# poor_man_DWM1001.net
KiCad netlist of a schematic drawn in EAGLE
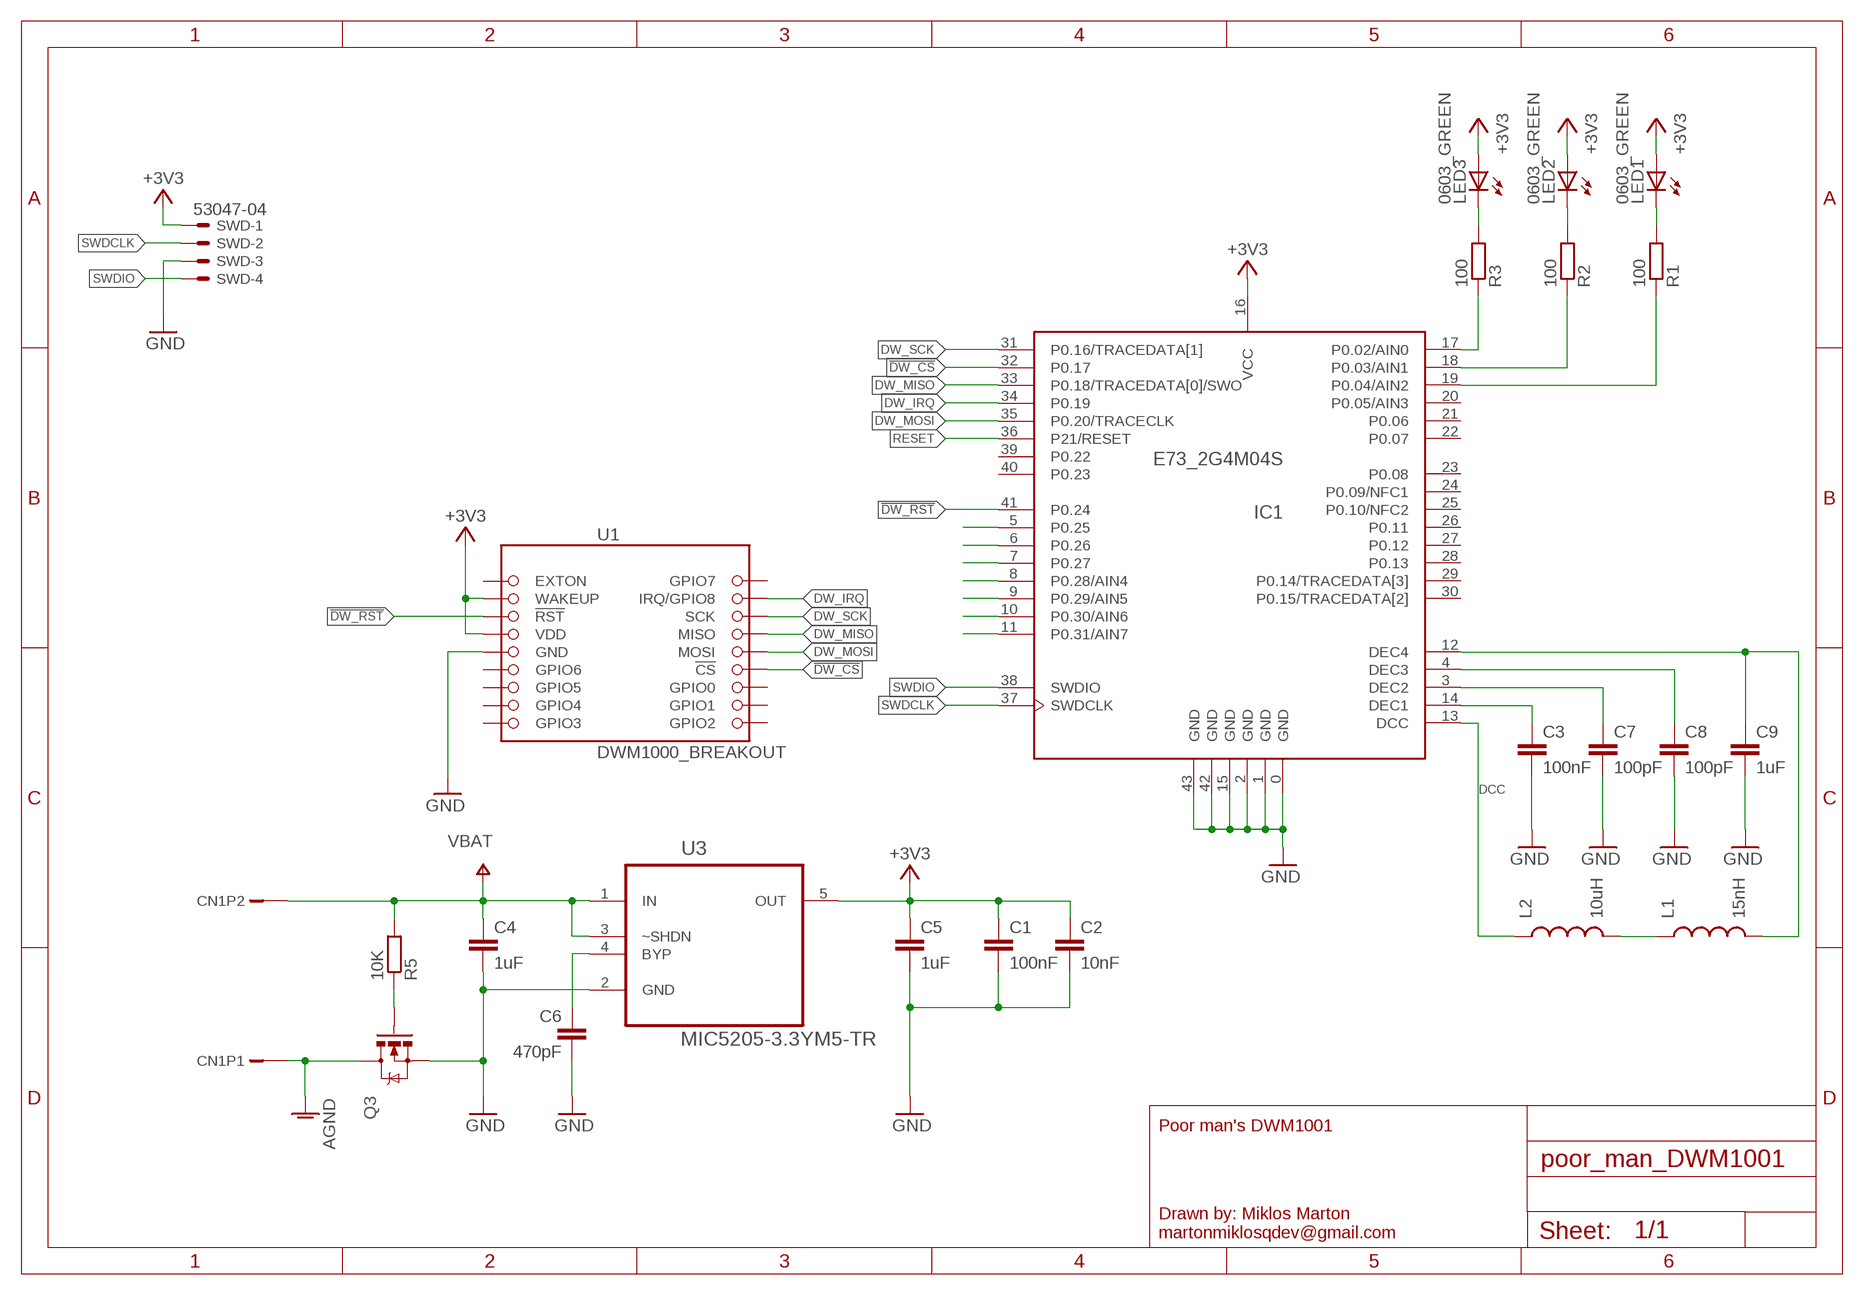
[diagram p0: schematic, sheet 1]

(export (version "E")
  (design (tool "Eeschema 10.0.6"))
  (components
    (comp (ref "C1")
      (value "100nF")
      (footprint "eagle-import:C0603")
      (libsource (lib "eagle-import") (part "C-EUC0603"))
    )
    (comp (ref "C2")
      (value "10nF")
      (footprint "eagle-import:C0603")
      (libsource (lib "eagle-import") (part "C-EUC0603"))
    )
    (comp (ref "C3")
      (value "100nF")
      (footprint "eagle-import:C0603")
      (libsource (lib "eagle-import") (part "C-EUC0603"))
    )
    (comp (ref "C4")
      (value "1uF")
      (footprint "eagle-import:C0603")
      (libsource (lib "eagle-import") (part "C-EUC0603"))
    )
    (comp (ref "C5")
      (value "1uF")
      (footprint "eagle-import:C0603")
      (libsource (lib "eagle-import") (part "C-EUC0603"))
    )
    (comp (ref "C6")
      (value "470pF")
      (footprint "eagle-import:C0603")
      (libsource (lib "eagle-import") (part "C-EUC0603"))
    )
    (comp (ref "C7")
      (value "100pF")
      (footprint "eagle-import:C0603")
      (libsource (lib "eagle-import") (part "C-EUC0603"))
    )
    (comp (ref "C8")
      (value "100pF")
      (footprint "eagle-import:C0603")
      (libsource (lib "eagle-import") (part "C-EUC0603"))
    )
    (comp (ref "C9")
      (value "1uF")
      (footprint "eagle-import:C0603")
      (libsource (lib "eagle-import") (part "C-EUC0603"))
    )
    (comp (ref "CN1")
      (value "B2B-PH-K-S")
      (footprint "eagle-import:B2B-PH-K-S")
      (libsource (lib "eagle-import") (part "B2B-PH-K-S"))
    )
    (comp (ref "IC1")
      (value "E73_2G4M04S")
      (footprint "eagle-import:E73_2G4M04S")
      (libsource (lib "eagle-import") (part "E73_2G4M04S"))
    )
    (comp (ref "L1")
      (value "15nH")
      (footprint "eagle-import:SPARKFUN_C0402")
      (libsource (lib "eagle-import") (part "SPARKFUN_INDUCTOR0402"))
    )
    (comp (ref "L2")
      (value "10uH")
      (footprint "eagle-import:SPARKFUN_0603")
      (libsource (lib "eagle-import") (part "SPARKFUN_INDUCTOR0603"))
    )
    (comp (ref "LED1")
      (value "0603_GREEN")
      (footprint "eagle-import:CHIP-LED0603")
      (libsource (lib "eagle-import") (part "LEDCHIP-LED0603"))
    )
    (comp (ref "LED2")
      (value "0603_GREEN")
      (footprint "eagle-import:CHIP-LED0603")
      (libsource (lib "eagle-import") (part "LEDCHIP-LED0603"))
    )
    (comp (ref "LED3")
      (value "0603_GREEN")
      (footprint "eagle-import:CHIP-LED0603")
      (libsource (lib "eagle-import") (part "LEDCHIP-LED0603"))
    )
    (comp (ref "Q3")
      (value "MOSFET-NCHANNELSMD")
      (footprint "eagle-import:SOT23-3")
      (libsource (lib "eagle-import") (part "MOSFET-NCHANNELSMD"))
    )
    (comp (ref "R1")
      (value "100")
      (footprint "eagle-import:R0603")
      (libsource (lib "eagle-import") (part "R-EU_R0603"))
    )
    (comp (ref "R2")
      (value "100")
      (footprint "eagle-import:R0603")
      (libsource (lib "eagle-import") (part "R-EU_R0603"))
    )
    (comp (ref "R3")
      (value "100")
      (footprint "eagle-import:R0603")
      (libsource (lib "eagle-import") (part "R-EU_R0603"))
    )
    (comp (ref "R5")
      (value "10K")
      (footprint "eagle-import:R0603")
      (libsource (lib "eagle-import") (part "R-EU_R0603"))
    )
    (comp (ref "SWD")
      (value "53047-04")
      (footprint "eagle-import:53047-04")
      (fields (field (name "MF") "WALDOM/MOLEX") (field (name "MPN") "53047-0410"))
      (libsource (lib "eagle-import") (part "53?-04047"))
    )
    (comp (ref "U1")
      (value "DWM1000_BREAKOUT")
      (footprint "eagle-import:DWM1000_BREAKOUT")
      (libsource (lib "eagle-import") (part "DWM1000_BREAKOUT"))
    )
    (comp (ref "U3")
      (value "MIC5205-3.3YM5-TR")
      (footprint "eagle-import:SOT95P280X145-5N")
      (fields (field (name "MPN") "LT1761ES5-3.3#TRMPBF"))
      (libsource (lib "eagle-import") (part "LT1761ES5-3.3TRMPBF"))
    )
  )
  (nets
    (net (code "1") (name "+3V3") (class "Default")
      (node (ref "C1") (pin "1") (pinfunction "1_1") (pintype "passive"))
      (node (ref "C2") (pin "1") (pinfunction "1_1") (pintype "passive"))
      (node (ref "C5") (pin "1") (pinfunction "1_1") (pintype "passive"))
      (node (ref "IC1") (pin "16") (pinfunction "VCC_16") (pintype "passive"))
      (node (ref "LED1") (pin "A") (pinfunction "A_A") (pintype "passive"))
      (node (ref "LED2") (pin "A") (pinfunction "A_A") (pintype "passive"))
      (node (ref "LED3") (pin "A") (pinfunction "A_A") (pintype "passive"))
      (node (ref "SWD") (pin "1") (pinfunction "S_1") (pintype "passive"))
      (node (ref "U1") (pin "15") (pinfunction "VDD_15") (pintype "passive"))
      (node (ref "U1") (pin "17") (pinfunction "WAKEUP_17") (pintype "passive"))
      (node (ref "U3") (pin "5") (pinfunction "OUT_5") (pintype "passive"))
    )
    (net (code "2") (name "/DCC") (class "Default")
      (node (ref "IC1") (pin "13") (pinfunction "DCC_13") (pintype "power_in"))
      (node (ref "L2") (pin "1") (pinfunction "1_1") (pintype "passive"))
    )
    (net (code "3") (name "/~{DW_CS}") (class "Default")
      (node (ref "IC1") (pin "32") (pinfunction "P0.17_32") (pintype "bidirectional"))
      (node (ref "U1") (pin "6") (pinfunction "~{CS}_6") (pintype "input"))
    )
    (net (code "4") (name "/~{DW_RST}") (class "Default")
      (node (ref "IC1") (pin "41") (pinfunction "P0.24_41") (pintype "bidirectional"))
      (node (ref "U1") (pin "16") (pinfunction "~{RST}_16") (pintype "input"))
    )
    (net (code "5") (name "AGND") (class "Default")
      (node (ref "CN1") (pin "1") (pinfunction "1_1") (pintype "passive"))
      (node (ref "Q3") (pin "3") (pinfunction "D_3") (pintype "passive"))
    )
    (net (code "6") (name "DW_IRQ") (class "Default")
      (node (ref "IC1") (pin "34") (pinfunction "P0.19_34") (pintype "bidirectional"))
      (node (ref "U1") (pin "2") (pinfunction "IRQ/GPIO8_2") (pintype "passive"))
    )
    (net (code "7") (name "DW_MISO") (class "Default")
      (node (ref "IC1") (pin "33") (pinfunction "P0.18/TRACEDATA[0]/SWO_33") (pintype "bidirectional"))
      (node (ref "U1") (pin "4") (pinfunction "MISO_4") (pintype "passive"))
    )
    (net (code "8") (name "DW_MOSI") (class "Default")
      (node (ref "IC1") (pin "35") (pinfunction "P0.20/TRACECLK_35") (pintype "bidirectional"))
      (node (ref "U1") (pin "5") (pinfunction "MOSI_5") (pintype "passive"))
    )
    (net (code "9") (name "DW_SCK") (class "Default")
      (node (ref "IC1") (pin "31") (pinfunction "P0.16/TRACEDATA[1]_31") (pintype "bidirectional"))
      (node (ref "U1") (pin "3") (pinfunction "SCK_3") (pintype "passive"))
    )
    (net (code "10") (name "GND") (class "Default")
      (node (ref "C1") (pin "2") (pinfunction "2_2") (pintype "passive"))
      (node (ref "C2") (pin "2") (pinfunction "2_2") (pintype "passive"))
      (node (ref "C3") (pin "2") (pinfunction "2_2") (pintype "passive"))
      (node (ref "C4") (pin "2") (pinfunction "2_2") (pintype "passive"))
      (node (ref "C5") (pin "2") (pinfunction "2_2") (pintype "passive"))
      (node (ref "C6") (pin "2") (pinfunction "2_2") (pintype "passive"))
      (node (ref "C7") (pin "2") (pinfunction "2_2") (pintype "passive"))
      (node (ref "C8") (pin "2") (pinfunction "2_2") (pintype "passive"))
      (node (ref "C9") (pin "2") (pinfunction "2_2") (pintype "passive"))
      (node (ref "IC1") (pin "0") (pinfunction "GND_0") (pintype "bidirectional"))
      (node (ref "IC1") (pin "1") (pinfunction "GND_1") (pintype "bidirectional"))
      (node (ref "IC1") (pin "15") (pinfunction "GND_15") (pintype "bidirectional"))
      (node (ref "IC1") (pin "2") (pinfunction "GND_2") (pintype "bidirectional"))
      (node (ref "IC1") (pin "42") (pinfunction "GND_42") (pintype "bidirectional"))
      (node (ref "IC1") (pin "43") (pinfunction "GND_43") (pintype "bidirectional"))
      (node (ref "Q3") (pin "2") (pinfunction "S_2") (pintype "passive"))
      (node (ref "SWD") (pin "3") (pinfunction "S_3") (pintype "passive"))
      (node (ref "U1") (pin "14") (pinfunction "GND_14") (pintype "passive"))
      (node (ref "U3") (pin "2") (pinfunction "GND_2") (pintype "passive"))
    )
    (net (code "11") (name "Net-(IC1-DEC1)") (class "Default")
      (node (ref "C3") (pin "1") (pinfunction "1_1") (pintype "passive"))
      (node (ref "IC1") (pin "14") (pinfunction "DEC1_14") (pintype "power_in"))
    )
    (net (code "12") (name "Net-(IC1-DEC2)") (class "Default")
      (node (ref "C7") (pin "1") (pinfunction "1_1") (pintype "passive"))
      (node (ref "IC1") (pin "3") (pinfunction "DEC2_3") (pintype "power_in"))
    )
    (net (code "13") (name "Net-(IC1-DEC3)") (class "Default")
      (node (ref "C8") (pin "1") (pinfunction "1_1") (pintype "passive"))
      (node (ref "IC1") (pin "4") (pinfunction "DEC3_4") (pintype "power_in"))
    )
    (net (code "14") (name "Net-(IC1-DEC4)") (class "Default")
      (node (ref "C9") (pin "1") (pinfunction "1_1") (pintype "passive"))
      (node (ref "IC1") (pin "12") (pinfunction "DEC4_12") (pintype "power_in"))
      (node (ref "L1") (pin "2") (pinfunction "2_2") (pintype "passive"))
    )
    (net (code "15") (name "Net-(IC1-P0.02{slash}AIN0)") (class "Default")
      (node (ref "IC1") (pin "17") (pinfunction "P0.02/AIN0_17") (pintype "bidirectional"))
      (node (ref "R3") (pin "1") (pinfunction "1_1") (pintype "passive"))
    )
    (net (code "16") (name "Net-(IC1-P0.03{slash}AIN1)") (class "Default")
      (node (ref "IC1") (pin "18") (pinfunction "P0.03/AIN1_18") (pintype "bidirectional"))
      (node (ref "R2") (pin "1") (pinfunction "1_1") (pintype "passive"))
    )
    (net (code "17") (name "Net-(IC1-P0.04{slash}AIN2)") (class "Default")
      (node (ref "IC1") (pin "19") (pinfunction "P0.04/AIN2_19") (pintype "bidirectional"))
      (node (ref "R1") (pin "1") (pinfunction "1_1") (pintype "passive"))
    )
    (net (code "18") (name "Net-(L1-Pad1)") (class "Default")
      (node (ref "L1") (pin "1") (pinfunction "1_1") (pintype "passive"))
      (node (ref "L2") (pin "2") (pinfunction "2_2") (pintype "passive"))
    )
    (net (code "19") (name "Net-(LED1-PadC)") (class "Default")
      (node (ref "LED1") (pin "C") (pinfunction "C_C") (pintype "passive"))
      (node (ref "R1") (pin "2") (pinfunction "2_2") (pintype "passive"))
    )
    (net (code "20") (name "Net-(LED2-PadC)") (class "Default")
      (node (ref "LED2") (pin "C") (pinfunction "C_C") (pintype "passive"))
      (node (ref "R2") (pin "2") (pinfunction "2_2") (pintype "passive"))
    )
    (net (code "21") (name "Net-(LED3-PadC)") (class "Default")
      (node (ref "LED3") (pin "C") (pinfunction "C_C") (pintype "passive"))
      (node (ref "R3") (pin "2") (pinfunction "2_2") (pintype "passive"))
    )
    (net (code "22") (name "Net-(Q3-G)") (class "Default")
      (node (ref "Q3") (pin "1") (pinfunction "G_1") (pintype "passive"))
      (node (ref "R5") (pin "1") (pinfunction "1_1") (pintype "passive"))
    )
    (net (code "23") (name "Net-(U3-BYP)") (class "Default")
      (node (ref "C6") (pin "1") (pinfunction "1_1") (pintype "passive"))
      (node (ref "U3") (pin "4") (pinfunction "BYP_4") (pintype "passive"))
    )
    (net (code "24") (name "RESET") (class "Default")
      (node (ref "IC1") (pin "36") (pinfunction "P21/RESET_36") (pintype "bidirectional"))
    )
    (net (code "25") (name "SWDCLK") (class "Default")
      (node (ref "IC1") (pin "37") (pinfunction "SWDCLK_37") (pintype "input"))
      (node (ref "SWD") (pin "2") (pinfunction "S_2") (pintype "passive"))
    )
    (net (code "26") (name "SWDIO") (class "Default")
      (node (ref "IC1") (pin "38") (pinfunction "SWDIO_38") (pintype "bidirectional"))
      (node (ref "SWD") (pin "4") (pinfunction "S_4") (pintype "passive"))
    )
    (net (code "27") (name "VBAT") (class "Default")
      (node (ref "C4") (pin "1") (pinfunction "1_1") (pintype "passive"))
      (node (ref "CN1") (pin "2") (pinfunction "1_2") (pintype "passive"))
      (node (ref "R5") (pin "2") (pinfunction "2_2") (pintype "passive"))
      (node (ref "U3") (pin "1") (pinfunction "IN_1") (pintype "power_in"))
      (node (ref "U3") (pin "3") (pinfunction "~{SHDN}_3") (pintype "input"))
    )
    (net (code "28") (name "unconnected-(IC1-P0.05{slash}AIN3-Pad20)") (class "Default")
      (node (ref "IC1") (pin "20") (pinfunction "P0.05/AIN3_20") (pintype "bidirectional"))
    )
    (net (code "29") (name "unconnected-(IC1-P0.06-Pad21)") (class "Default")
      (node (ref "IC1") (pin "21") (pinfunction "P0.06_21") (pintype "bidirectional"))
    )
    (net (code "30") (name "unconnected-(IC1-P0.07-Pad22)") (class "Default")
      (node (ref "IC1") (pin "22") (pinfunction "P0.07_22") (pintype "bidirectional"))
    )
    (net (code "31") (name "unconnected-(IC1-P0.08-Pad23)") (class "Default")
      (node (ref "IC1") (pin "23") (pinfunction "P0.08_23") (pintype "bidirectional"))
    )
    (net (code "32") (name "unconnected-(IC1-P0.09{slash}NFC1-Pad24)") (class "Default")
      (node (ref "IC1") (pin "24") (pinfunction "P0.09/NFC1_24") (pintype "bidirectional"))
    )
    (net (code "33") (name "unconnected-(IC1-P0.10{slash}NFC2-Pad25)") (class "Default")
      (node (ref "IC1") (pin "25") (pinfunction "P0.10/NFC2_25") (pintype "bidirectional"))
    )
    (net (code "34") (name "unconnected-(IC1-P0.11-Pad26)") (class "Default")
      (node (ref "IC1") (pin "26") (pinfunction "P0.11_26") (pintype "bidirectional"))
    )
    (net (code "35") (name "unconnected-(IC1-P0.12-Pad27)") (class "Default")
      (node (ref "IC1") (pin "27") (pinfunction "P0.12_27") (pintype "bidirectional"))
    )
    (net (code "36") (name "unconnected-(IC1-P0.13-Pad28)") (class "Default")
      (node (ref "IC1") (pin "28") (pinfunction "P0.13_28") (pintype "bidirectional"))
    )
    (net (code "37") (name "unconnected-(IC1-P0.14{slash}TRACEDATA[3]-Pad29)") (class "Default")
      (node (ref "IC1") (pin "29") (pinfunction "P0.14/TRACEDATA[3]_29") (pintype "bidirectional"))
    )
    (net (code "38") (name "unconnected-(IC1-P0.15{slash}TRACEDATA[2]-Pad30)") (class "Default")
      (node (ref "IC1") (pin "30") (pinfunction "P0.15/TRACEDATA[2]_30") (pintype "bidirectional"))
    )
    (net (code "39") (name "unconnected-(IC1-P0.22-Pad39)") (class "Default")
      (node (ref "IC1") (pin "39") (pinfunction "P0.22_39") (pintype "bidirectional"))
    )
    (net (code "40") (name "unconnected-(IC1-P0.23-Pad40)") (class "Default")
      (node (ref "IC1") (pin "40") (pinfunction "P0.23_40") (pintype "bidirectional"))
    )
    (net (code "41") (name "unconnected-(IC1-P0.25-Pad5)") (class "Default")
      (node (ref "IC1") (pin "5") (pinfunction "P0.25_5") (pintype "bidirectional"))
    )
    (net (code "42") (name "unconnected-(IC1-P0.26-Pad6)") (class "Default")
      (node (ref "IC1") (pin "6") (pinfunction "P0.26_6") (pintype "bidirectional"))
    )
    (net (code "43") (name "unconnected-(IC1-P0.27-Pad7)") (class "Default")
      (node (ref "IC1") (pin "7") (pinfunction "P0.27_7") (pintype "bidirectional"))
    )
    (net (code "44") (name "unconnected-(IC1-P0.28{slash}AIN4-Pad8)") (class "Default")
      (node (ref "IC1") (pin "8") (pinfunction "P0.28/AIN4_8") (pintype "bidirectional"))
    )
    (net (code "45") (name "unconnected-(IC1-P0.29{slash}AIN5-Pad9)") (class "Default")
      (node (ref "IC1") (pin "9") (pinfunction "P0.29/AIN5_9") (pintype "bidirectional"))
    )
    (net (code "46") (name "unconnected-(IC1-P0.30{slash}AIN6-Pad10)") (class "Default")
      (node (ref "IC1") (pin "10") (pinfunction "P0.30/AIN6_10") (pintype "bidirectional"))
    )
    (net (code "47") (name "unconnected-(IC1-P0.31{slash}AIN7-Pad11)") (class "Default")
      (node (ref "IC1") (pin "11") (pinfunction "P0.31/AIN7_11") (pintype "bidirectional"))
    )
    (net (code "48") (name "unconnected-(U1-EXTON-Pad18)") (class "Default")
      (node (ref "U1") (pin "18") (pinfunction "EXTON_18") (pintype "passive"))
    )
    (net (code "49") (name "unconnected-(U1-GPIO0-Pad7)") (class "Default")
      (node (ref "U1") (pin "7") (pinfunction "GPIO0_7") (pintype "passive"))
    )
    (net (code "50") (name "unconnected-(U1-GPIO1-Pad8)") (class "Default")
      (node (ref "U1") (pin "8") (pinfunction "GPIO1_8") (pintype "passive"))
    )
    (net (code "51") (name "unconnected-(U1-GPIO2-Pad9)") (class "Default")
      (node (ref "U1") (pin "9") (pinfunction "GPIO2_9") (pintype "passive"))
    )
    (net (code "52") (name "unconnected-(U1-GPIO3-Pad10)") (class "Default")
      (node (ref "U1") (pin "10") (pinfunction "GPIO3_10") (pintype "passive"))
    )
    (net (code "53") (name "unconnected-(U1-GPIO4-Pad11)") (class "Default")
      (node (ref "U1") (pin "11") (pinfunction "GPIO4_11") (pintype "passive"))
    )
    (net (code "54") (name "unconnected-(U1-GPIO5-Pad12)") (class "Default")
      (node (ref "U1") (pin "12") (pinfunction "GPIO5_12") (pintype "passive"))
    )
    (net (code "55") (name "unconnected-(U1-GPIO6-Pad13)") (class "Default")
      (node (ref "U1") (pin "13") (pinfunction "GPIO6_13") (pintype "passive"))
    )
    (net (code "56") (name "unconnected-(U1-GPIO7-Pad1)") (class "Default")
      (node (ref "U1") (pin "1") (pinfunction "GPIO7_1") (pintype "passive"))
    )
  )
)
